# ARM_EURO_Platine4.net
KiCad netlist of a schematic drawn in Altium Designer
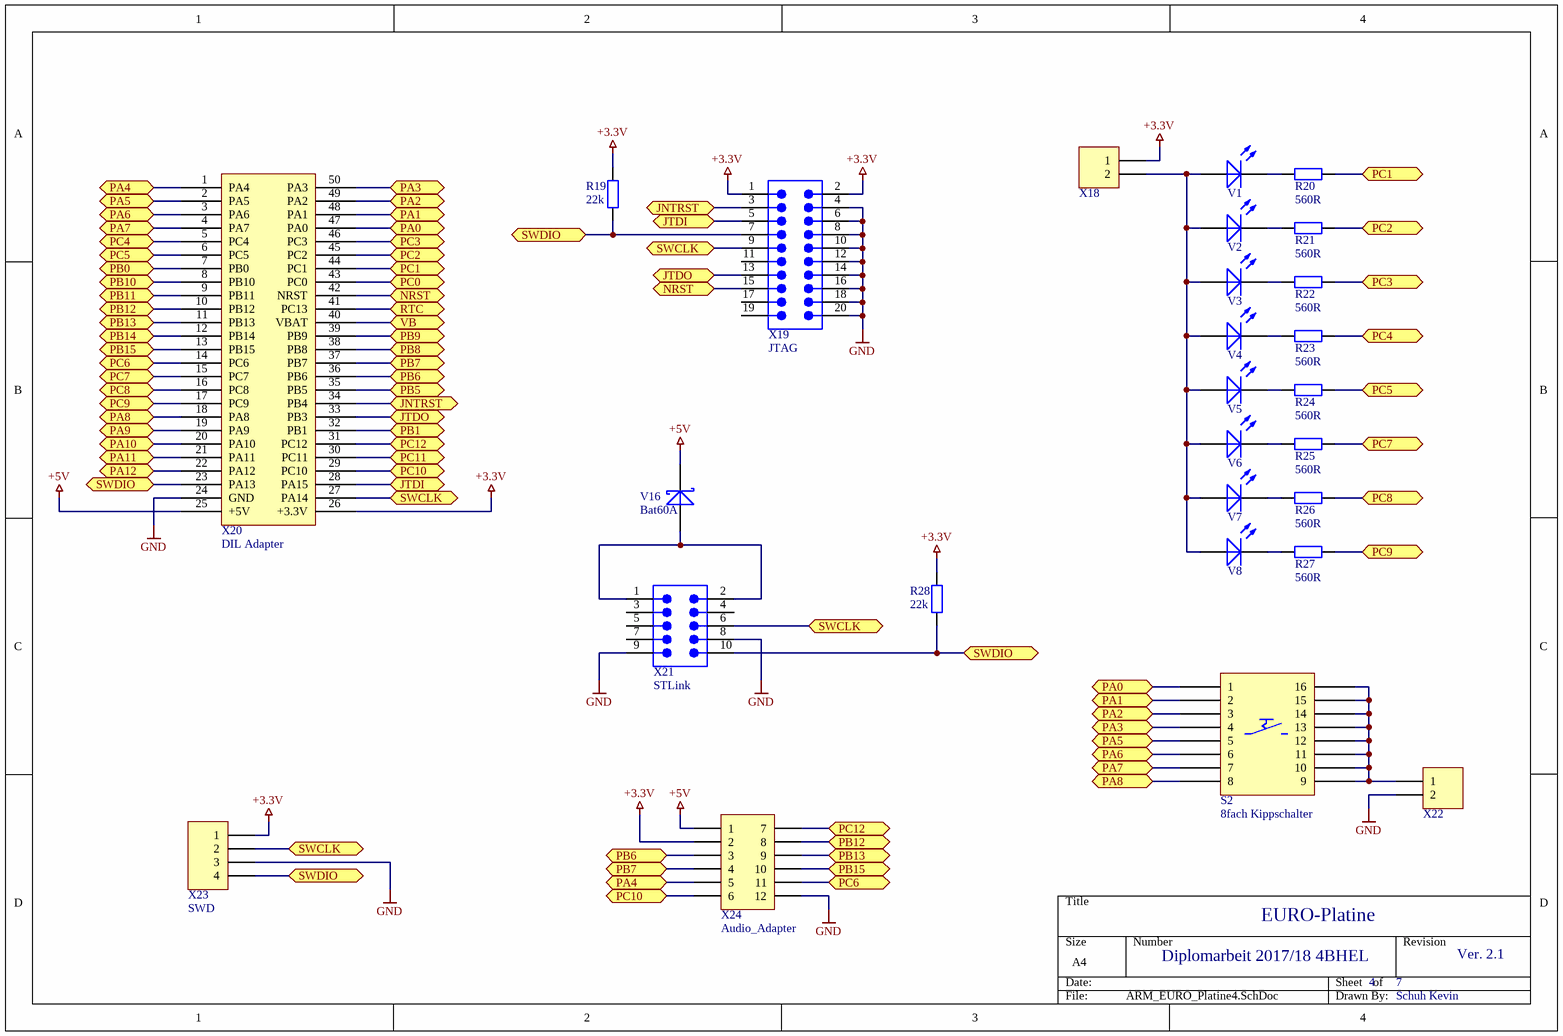
[diagram p0: ARM_EURO_Platine4.SchDoc]

(export (version "E")
  (design (tool "Eeschema 10.0.6"))
  (components
    (comp (ref "R19")
      (value "22k")
      (footprint "0805_Res")
      (description "Resistor")
      (fields (field (name "Comment") "Res_SMD") (field (name "PUBLISHER") "Altium Limited"))
      (libsource (lib "") (part "Res_SMD_1"))
    )
    (comp (ref "R20")
      (value "560R")
      (footprint "0805_Res")
      (description "Resistor")
      (fields (field (name "Comment") "Res_SMD") (field (name "PUBLISHER") "Altium Limited"))
      (libsource (lib "ARM_Libary_EURO") (part "Res_SMD"))
    )
    (comp (ref "R21")
      (value "560R")
      (footprint "0805_Res")
      (description "Resistor")
      (fields (field (name "Comment") "Res_SMD") (field (name "PUBLISHER") "Altium Limited"))
      (libsource (lib "ARM_Libary_EURO") (part "Res_SMD"))
    )
    (comp (ref "R22")
      (value "560R")
      (footprint "0805_Res")
      (description "Resistor")
      (fields (field (name "Comment") "Res_SMD") (field (name "PUBLISHER") "Altium Limited"))
      (libsource (lib "ARM_Libary_EURO") (part "Res_SMD"))
    )
    (comp (ref "R23")
      (value "560R")
      (footprint "0805_Res")
      (description "Resistor")
      (fields (field (name "Comment") "Res_SMD") (field (name "PUBLISHER") "Altium Limited"))
      (libsource (lib "ARM_Libary_EURO") (part "Res_SMD"))
    )
    (comp (ref "R24")
      (value "560R")
      (footprint "0805_Res")
      (description "Resistor")
      (fields (field (name "Comment") "Res_SMD") (field (name "PUBLISHER") "Altium Limited"))
      (libsource (lib "ARM_Libary_EURO") (part "Res_SMD"))
    )
    (comp (ref "R25")
      (value "560R")
      (footprint "0805_Res")
      (description "Resistor")
      (fields (field (name "Comment") "Res_SMD") (field (name "PUBLISHER") "Altium Limited"))
      (libsource (lib "ARM_Libary_EURO") (part "Res_SMD"))
    )
    (comp (ref "R26")
      (value "560R")
      (footprint "0805_Res")
      (description "Resistor")
      (fields (field (name "Comment") "Res_SMD") (field (name "PUBLISHER") "Altium Limited"))
      (libsource (lib "ARM_Libary_EURO") (part "Res_SMD"))
    )
    (comp (ref "R27")
      (value "560R")
      (footprint "0805_Res")
      (description "Resistor")
      (fields (field (name "Comment") "Res_SMD") (field (name "PUBLISHER") "Altium Limited"))
      (libsource (lib "ARM_Libary_EURO") (part "Res_SMD"))
    )
    (comp (ref "R28")
      (value "22k")
      (footprint "0805_Res")
      (description "Resistor")
      (fields (field (name "Comment") "Res_SMD") (field (name "PUBLISHER") "Altium Limited"))
      (libsource (lib "") (part "Res_SMD_1"))
    )
    (comp (ref "S2")
      (value "8fach Kippschalter")
      (footprint "DIP_16")
      (libsource (lib "ARM_Libary_EURO") (part "Kippschalter_8fach"))
    )
    (comp (ref "V1")
      (value "LED")
      (footprint "0805_LED")
      (description "Typical RED, GREEN, YELLOW, AMBER GaAs LED")
      (fields (field (name "PUBLISHER") "Altium Limited"))
      (libsource (lib "ARM_Libary_EURO") (part "LED_SMD"))
    )
    (comp (ref "V2")
      (value "LED")
      (footprint "0805_LED")
      (description "Typical RED, GREEN, YELLOW, AMBER GaAs LED")
      (fields (field (name "PUBLISHER") "Altium Limited"))
      (libsource (lib "ARM_Libary_EURO") (part "LED_SMD"))
    )
    (comp (ref "V3")
      (value "LED")
      (footprint "0805_LED")
      (description "Typical RED, GREEN, YELLOW, AMBER GaAs LED")
      (fields (field (name "PUBLISHER") "Altium Limited"))
      (libsource (lib "ARM_Libary_EURO") (part "LED_SMD"))
    )
    (comp (ref "V4")
      (value "LED")
      (footprint "0805_LED")
      (description "Typical RED, GREEN, YELLOW, AMBER GaAs LED")
      (fields (field (name "PUBLISHER") "Altium Limited"))
      (libsource (lib "ARM_Libary_EURO") (part "LED_SMD"))
    )
    (comp (ref "V5")
      (value "LED")
      (footprint "0805_LED")
      (description "Typical RED, GREEN, YELLOW, AMBER GaAs LED")
      (fields (field (name "PUBLISHER") "Altium Limited"))
      (libsource (lib "ARM_Libary_EURO") (part "LED_SMD"))
    )
    (comp (ref "V6")
      (value "LED")
      (footprint "0805_LED")
      (description "Typical RED, GREEN, YELLOW, AMBER GaAs LED")
      (fields (field (name "PUBLISHER") "Altium Limited"))
      (libsource (lib "ARM_Libary_EURO") (part "LED_SMD"))
    )
    (comp (ref "V7")
      (value "LED")
      (footprint "0805_LED")
      (description "Typical RED, GREEN, YELLOW, AMBER GaAs LED")
      (fields (field (name "PUBLISHER") "Altium Limited"))
      (libsource (lib "ARM_Libary_EURO") (part "LED_SMD"))
    )
    (comp (ref "V8")
      (value "LED")
      (footprint "0805_LED")
      (description "Typical RED, GREEN, YELLOW, AMBER GaAs LED")
      (fields (field (name "PUBLISHER") "Altium Limited"))
      (libsource (lib "ARM_Libary_EURO") (part "LED_SMD"))
    )
    (comp (ref "V16")
      (value "Bat60A")
      (footprint "BAT254_Schottky")
      (description "Diode")
      (libsource (lib "ARM_Libary_EURO") (part "Bat60A"))
    )
    (comp (ref "X18")
      (value "Header")
      (footprint "HDR1X2")
      (description "Header, 2-Pin")
      (fields (field (name "PUBLISHER") "Altium Limited"))
      (libsource (lib "") (part "Header_2_1"))
    )
    (comp (ref "X19")
      (value "JTAG")
      (footprint "JTAG_90Grad")
      (fields (field (name "PUBLISHER") "Altium Limited"))
      (libsource (lib "ARM_Libary_EURO") (part "JTAG"))
    )
    (comp (ref "X20")
      (value "DIL Adapter")
      (footprint "DIL_Adapter_V03")
      (description "DIL Adapter 50 Pin")
      (libsource (lib "ARM_Libary_EURO") (part "DIL_Adapter_V03"))
    )
    (comp (ref "X21")
      (value "STLink")
      (footprint "STLink")
      (fields (field (name "PUBLISHER") "Altium Limited"))
      (libsource (lib "ARM_Libary_EURO") (part "STLink"))
    )
    (comp (ref "X22")
      (value "Header")
      (footprint "HDR1X2")
      (description "Header, 2-Pin")
      (fields (field (name "PUBLISHER") "Altium Limited"))
      (libsource (lib "ARM_Libary_EURO") (part "Header_2"))
    )
    (comp (ref "X23")
      (value "SWD")
      (footprint "HDR1X4_SWD")
      (description "Header, 4-Pin")
      (fields (field (name "PUBLISHER") "Altium Limited"))
      (libsource (lib "ARM_Libary_DIL") (part "SWD"))
    )
    (comp (ref "X24")
      (value "Audio_Adapter")
      (footprint "AUDIO_ADAPTER")
      (description "Header, 6-Pin, Dual row")
      (fields (field (name "PUBLISHER") "Altium Limited"))
      (libsource (lib "ARM_Libary_EURO") (part "Audio_Adapter"))
    )
  )
  (nets
    (net (code "1") (name "+3.3V") (class "Default")
      (node (ref "R19") (pin "2") (pinfunction "2_2") (pintype "passive"))
      (node (ref "R28") (pin "2") (pinfunction "2_2") (pintype "passive"))
      (node (ref "X18") (pin "1") (pinfunction "1_1") (pintype "passive"))
      (node (ref "X19") (pin "1") (pinfunction "1_1") (pintype "passive"))
      (node (ref "X19") (pin "2") (pinfunction "2_2") (pintype "passive"))
      (node (ref "X20") (pin "26") (pinfunction "+3.3V_26") (pintype "passive"))
      (node (ref "X23") (pin "1") (pinfunction "1_1") (pintype "passive"))
      (node (ref "X24") (pin "2") (pinfunction "2_2") (pintype "passive"))
    )
    (net (code "2") (name "+5V") (class "Default")
      (node (ref "V16") (pin "1") (pinfunction "1_1") (pintype "passive"))
      (node (ref "X20") (pin "25") (pinfunction "+5V_25") (pintype "passive"))
      (node (ref "X24") (pin "1") (pinfunction "1_1") (pintype "passive"))
    )
    (net (code "3") (name "/JNTRST") (class "Default")
      (node (ref "X19") (pin "3") (pinfunction "3_3") (pintype "passive"))
      (node (ref "X20") (pin "34") (pinfunction "PB4_34") (pintype "passive"))
    )
    (net (code "4") (name "/JTDI") (class "Default")
      (node (ref "X19") (pin "5") (pinfunction "5_5") (pintype "passive"))
      (node (ref "X20") (pin "28") (pinfunction "PA15_28") (pintype "passive"))
    )
    (net (code "5") (name "/JTDO") (class "Default")
      (node (ref "X19") (pin "13") (pinfunction "13_13") (pintype "passive"))
      (node (ref "X20") (pin "33") (pinfunction "PB3_33") (pintype "passive"))
    )
    (net (code "6") (name "/NRST") (class "Default")
      (node (ref "X19") (pin "15") (pinfunction "15_15") (pintype "passive"))
      (node (ref "X20") (pin "42") (pinfunction "NRST_42") (pintype "passive"))
    )
    (net (code "7") (name "/PA0") (class "Default")
      (node (ref "S2") (pin "1") (pinfunction "1_1") (pintype "passive"))
      (node (ref "X20") (pin "47") (pinfunction "PA0_47") (pintype "passive"))
    )
    (net (code "8") (name "/PA1") (class "Default")
      (node (ref "S2") (pin "2") (pinfunction "2_2") (pintype "passive"))
      (node (ref "X20") (pin "48") (pinfunction "PA1_48") (pintype "passive"))
    )
    (net (code "9") (name "/PA2") (class "Default")
      (node (ref "S2") (pin "3") (pinfunction "3_3") (pintype "passive"))
      (node (ref "X20") (pin "49") (pinfunction "PA2_49") (pintype "passive"))
    )
    (net (code "10") (name "/PA3") (class "Default")
      (node (ref "S2") (pin "4") (pinfunction "4_4") (pintype "passive"))
      (node (ref "X20") (pin "50") (pinfunction "PA3_50") (pintype "passive"))
    )
    (net (code "11") (name "/PA4") (class "Default")
      (node (ref "X20") (pin "1") (pinfunction "PA4_1") (pintype "passive"))
      (node (ref "X24") (pin "5") (pinfunction "5_5") (pintype "passive"))
    )
    (net (code "12") (name "/PA5") (class "Default")
      (node (ref "S2") (pin "5") (pinfunction "5_5") (pintype "passive"))
      (node (ref "X20") (pin "2") (pinfunction "PA5_2") (pintype "passive"))
    )
    (net (code "13") (name "/PA6") (class "Default")
      (node (ref "S2") (pin "6") (pinfunction "6_6") (pintype "passive"))
      (node (ref "X20") (pin "3") (pinfunction "PA6_3") (pintype "passive"))
    )
    (net (code "14") (name "/PA7") (class "Default")
      (node (ref "S2") (pin "7") (pinfunction "7_7") (pintype "passive"))
      (node (ref "X20") (pin "4") (pinfunction "PA7_4") (pintype "passive"))
    )
    (net (code "15") (name "/PA8") (class "Default")
      (node (ref "S2") (pin "8") (pinfunction "8_8") (pintype "passive"))
      (node (ref "X20") (pin "18") (pinfunction "PA8_18") (pintype "passive"))
    )
    (net (code "16") (name "/PA9") (class "Default")
      (node (ref "X20") (pin "19") (pinfunction "PA9_19") (pintype "passive"))
    )
    (net (code "17") (name "/PA10") (class "Default")
      (node (ref "X20") (pin "20") (pinfunction "PA10_20") (pintype "passive"))
    )
    (net (code "18") (name "/PA11") (class "Default")
      (node (ref "X20") (pin "21") (pinfunction "PA11_21") (pintype "passive"))
    )
    (net (code "19") (name "/PA12") (class "Default")
      (node (ref "X20") (pin "22") (pinfunction "PA12_22") (pintype "passive"))
    )
    (net (code "20") (name "/PB0") (class "Default")
      (node (ref "X20") (pin "7") (pinfunction "PB0_7") (pintype "passive"))
    )
    (net (code "21") (name "/PB1") (class "Default")
      (node (ref "X20") (pin "32") (pinfunction "PB1_32") (pintype "passive"))
    )
    (net (code "22") (name "/PB5") (class "Default")
      (node (ref "X20") (pin "35") (pinfunction "PB5_35") (pintype "passive"))
    )
    (net (code "23") (name "/PB6") (class "Default")
      (node (ref "X20") (pin "36") (pinfunction "PB6_36") (pintype "passive"))
      (node (ref "X24") (pin "3") (pinfunction "3_3") (pintype "passive"))
    )
    (net (code "24") (name "/PB7") (class "Default")
      (node (ref "X20") (pin "37") (pinfunction "PB7_37") (pintype "passive"))
      (node (ref "X24") (pin "4") (pinfunction "4_4") (pintype "passive"))
    )
    (net (code "25") (name "/PB8") (class "Default")
      (node (ref "X20") (pin "38") (pinfunction "PB8_38") (pintype "passive"))
    )
    (net (code "26") (name "/PB9") (class "Default")
      (node (ref "X20") (pin "39") (pinfunction "PB9_39") (pintype "passive"))
    )
    (net (code "27") (name "/PB10") (class "Default")
      (node (ref "X20") (pin "8") (pinfunction "PB10_8") (pintype "passive"))
    )
    (net (code "28") (name "/PB11") (class "Default")
      (node (ref "X20") (pin "9") (pinfunction "PB11_9") (pintype "passive"))
    )
    (net (code "29") (name "/PB12") (class "Default")
      (node (ref "X20") (pin "10") (pinfunction "PB12_10") (pintype "passive"))
      (node (ref "X24") (pin "8") (pinfunction "8_8") (pintype "passive"))
    )
    (net (code "30") (name "/PB13") (class "Default")
      (node (ref "X20") (pin "11") (pinfunction "PB13_11") (pintype "passive"))
      (node (ref "X24") (pin "9") (pinfunction "9_9") (pintype "passive"))
    )
    (net (code "31") (name "/PB14") (class "Default")
      (node (ref "X20") (pin "12") (pinfunction "PB14_12") (pintype "passive"))
    )
    (net (code "32") (name "/PB15") (class "Default")
      (node (ref "X20") (pin "13") (pinfunction "PB15_13") (pintype "passive"))
      (node (ref "X24") (pin "10") (pinfunction "10_10") (pintype "passive"))
    )
    (net (code "33") (name "/PC0") (class "Default")
      (node (ref "X20") (pin "43") (pinfunction "PC0_43") (pintype "passive"))
    )
    (net (code "34") (name "/PC1") (class "Default")
      (node (ref "R20") (pin "2") (pinfunction "2_2") (pintype "passive"))
      (node (ref "X20") (pin "44") (pinfunction "PC1_44") (pintype "passive"))
    )
    (net (code "35") (name "/PC2") (class "Default")
      (node (ref "R21") (pin "2") (pinfunction "2_2") (pintype "passive"))
      (node (ref "X20") (pin "45") (pinfunction "PC2_45") (pintype "passive"))
    )
    (net (code "36") (name "/PC3") (class "Default")
      (node (ref "R22") (pin "2") (pinfunction "2_2") (pintype "passive"))
      (node (ref "X20") (pin "46") (pinfunction "PC3_46") (pintype "passive"))
    )
    (net (code "37") (name "/PC4") (class "Default")
      (node (ref "R23") (pin "2") (pinfunction "2_2") (pintype "passive"))
      (node (ref "X20") (pin "5") (pinfunction "PC4_5") (pintype "passive"))
    )
    (net (code "38") (name "/PC5") (class "Default")
      (node (ref "R24") (pin "2") (pinfunction "2_2") (pintype "passive"))
      (node (ref "X20") (pin "6") (pinfunction "PC5_6") (pintype "passive"))
    )
    (net (code "39") (name "/PC6") (class "Default")
      (node (ref "X20") (pin "14") (pinfunction "PC6_14") (pintype "passive"))
      (node (ref "X24") (pin "11") (pinfunction "11_11") (pintype "passive"))
    )
    (net (code "40") (name "/PC7") (class "Default")
      (node (ref "R25") (pin "2") (pinfunction "2_2") (pintype "passive"))
      (node (ref "X20") (pin "15") (pinfunction "PC7_15") (pintype "passive"))
    )
    (net (code "41") (name "/PC8") (class "Default")
      (node (ref "R26") (pin "2") (pinfunction "2_2") (pintype "passive"))
      (node (ref "X20") (pin "16") (pinfunction "PC8_16") (pintype "passive"))
    )
    (net (code "42") (name "/PC9") (class "Default")
      (node (ref "R27") (pin "2") (pinfunction "2_2") (pintype "passive"))
      (node (ref "X20") (pin "17") (pinfunction "PC9_17") (pintype "passive"))
    )
    (net (code "43") (name "/PC10") (class "Default")
      (node (ref "X20") (pin "29") (pinfunction "PC10_29") (pintype "passive"))
      (node (ref "X24") (pin "6") (pinfunction "6_6") (pintype "passive"))
    )
    (net (code "44") (name "/PC11") (class "Default")
      (node (ref "X20") (pin "30") (pinfunction "PC11_30") (pintype "passive"))
    )
    (net (code "45") (name "/PC12") (class "Default")
      (node (ref "X20") (pin "31") (pinfunction "PC12_31") (pintype "passive"))
      (node (ref "X24") (pin "7") (pinfunction "7_7") (pintype "passive"))
    )
    (net (code "46") (name "/RTC") (class "Default")
      (node (ref "X20") (pin "41") (pinfunction "PC13_41") (pintype "passive"))
    )
    (net (code "47") (name "/SWCLK") (class "Default")
      (node (ref "X19") (pin "9") (pinfunction "9_9") (pintype "passive"))
      (node (ref "X20") (pin "27") (pinfunction "PA14_27") (pintype "passive"))
      (node (ref "X21") (pin "6") (pinfunction "6_6") (pintype "passive"))
      (node (ref "X23") (pin "2") (pinfunction "2_2") (pintype "passive"))
    )
    (net (code "48") (name "/SWDIO") (class "Default")
      (node (ref "R19") (pin "1") (pinfunction "1_1") (pintype "passive"))
      (node (ref "R28") (pin "1") (pinfunction "1_1") (pintype "passive"))
      (node (ref "X19") (pin "7") (pinfunction "7_7") (pintype "passive"))
      (node (ref "X20") (pin "23") (pinfunction "PA13_23") (pintype "passive"))
      (node (ref "X21") (pin "10") (pinfunction "10_10") (pintype "passive"))
      (node (ref "X23") (pin "4") (pinfunction "4_4") (pintype "passive"))
    )
    (net (code "49") (name "/VB") (class "Default")
      (node (ref "X20") (pin "40") (pinfunction "VBAT_40") (pintype "passive"))
    )
    (net (code "50") (name "GND") (class "Default")
      (node (ref "X19") (pin "10") (pinfunction "10_10") (pintype "passive"))
      (node (ref "X19") (pin "12") (pinfunction "12_12") (pintype "passive"))
      (node (ref "X19") (pin "14") (pinfunction "14_14") (pintype "passive"))
      (node (ref "X19") (pin "16") (pinfunction "16_16") (pintype "passive"))
      (node (ref "X19") (pin "18") (pinfunction "18_18") (pintype "passive"))
      (node (ref "X19") (pin "20") (pinfunction "20_20") (pintype "passive"))
      (node (ref "X19") (pin "4") (pinfunction "4_4") (pintype "passive"))
      (node (ref "X19") (pin "6") (pinfunction "6_6") (pintype "passive"))
      (node (ref "X19") (pin "8") (pinfunction "8_8") (pintype "passive"))
      (node (ref "X20") (pin "24") (pinfunction "GND_24") (pintype "passive"))
      (node (ref "X21") (pin "8") (pinfunction "8_8") (pintype "passive"))
      (node (ref "X21") (pin "9") (pinfunction "9_9") (pintype "passive"))
      (node (ref "X22") (pin "2") (pinfunction "2_2") (pintype "passive"))
      (node (ref "X23") (pin "3") (pinfunction "3_3") (pintype "passive"))
      (node (ref "X24") (pin "12") (pinfunction "12_12") (pintype "passive"))
    )
    (net (code "51") (name "Net-(S2-Pad10)") (class "Default")
      (node (ref "S2") (pin "10") (pinfunction "10_10") (pintype "passive"))
      (node (ref "S2") (pin "11") (pinfunction "11_11") (pintype "passive"))
      (node (ref "S2") (pin "12") (pinfunction "12_12") (pintype "passive"))
      (node (ref "S2") (pin "13") (pinfunction "13_13") (pintype "passive"))
      (node (ref "S2") (pin "14") (pinfunction "14_14") (pintype "passive"))
      (node (ref "S2") (pin "15") (pinfunction "15_15") (pintype "passive"))
      (node (ref "S2") (pin "16") (pinfunction "16_16") (pintype "passive"))
      (node (ref "S2") (pin "9") (pinfunction "9_9") (pintype "passive"))
      (node (ref "X22") (pin "1") (pinfunction "1_1") (pintype "passive"))
    )
    (net (code "52") (name "Net-(V1-A)") (class "Default")
      (node (ref "V1") (pin "1") (pinfunction "A_1") (pintype "passive"))
      (node (ref "V2") (pin "1") (pinfunction "A_1") (pintype "passive"))
      (node (ref "V3") (pin "1") (pinfunction "A_1") (pintype "passive"))
      (node (ref "V4") (pin "1") (pinfunction "A_1") (pintype "passive"))
      (node (ref "V5") (pin "1") (pinfunction "A_1") (pintype "passive"))
      (node (ref "V6") (pin "1") (pinfunction "A_1") (pintype "passive"))
      (node (ref "V7") (pin "1") (pinfunction "A_1") (pintype "passive"))
      (node (ref "V8") (pin "1") (pinfunction "A_1") (pintype "passive"))
      (node (ref "X18") (pin "2") (pinfunction "2_2") (pintype "passive"))
    )
    (net (code "53") (name "Net-(V1-K)") (class "Default")
      (node (ref "R20") (pin "1") (pinfunction "1_1") (pintype "passive"))
      (node (ref "V1") (pin "2") (pinfunction "K_2") (pintype "passive"))
    )
    (net (code "54") (name "Net-(V2-K)") (class "Default")
      (node (ref "R21") (pin "1") (pinfunction "1_1") (pintype "passive"))
      (node (ref "V2") (pin "2") (pinfunction "K_2") (pintype "passive"))
    )
    (net (code "55") (name "Net-(V3-K)") (class "Default")
      (node (ref "R22") (pin "1") (pinfunction "1_1") (pintype "passive"))
      (node (ref "V3") (pin "2") (pinfunction "K_2") (pintype "passive"))
    )
    (net (code "56") (name "Net-(V4-K)") (class "Default")
      (node (ref "R23") (pin "1") (pinfunction "1_1") (pintype "passive"))
      (node (ref "V4") (pin "2") (pinfunction "K_2") (pintype "passive"))
    )
    (net (code "57") (name "Net-(V5-K)") (class "Default")
      (node (ref "R24") (pin "1") (pinfunction "1_1") (pintype "passive"))
      (node (ref "V5") (pin "2") (pinfunction "K_2") (pintype "passive"))
    )
    (net (code "58") (name "Net-(V6-K)") (class "Default")
      (node (ref "R25") (pin "1") (pinfunction "1_1") (pintype "passive"))
      (node (ref "V6") (pin "2") (pinfunction "K_2") (pintype "passive"))
    )
    (net (code "59") (name "Net-(V7-K)") (class "Default")
      (node (ref "R26") (pin "1") (pinfunction "1_1") (pintype "passive"))
      (node (ref "V7") (pin "2") (pinfunction "K_2") (pintype "passive"))
    )
    (net (code "60") (name "Net-(V8-K)") (class "Default")
      (node (ref "R27") (pin "1") (pinfunction "1_1") (pintype "passive"))
      (node (ref "V8") (pin "2") (pinfunction "K_2") (pintype "passive"))
    )
    (net (code "61") (name "Net-(V16-Pad2)") (class "Default")
      (node (ref "V16") (pin "2") (pinfunction "2_2") (pintype "passive"))
      (node (ref "X21") (pin "1") (pinfunction "1_1") (pintype "passive"))
      (node (ref "X21") (pin "2") (pinfunction "2_2") (pintype "passive"))
    )
    (net (code "62") (name "unconnected-(X19-Pad11)") (class "Default")
      (node (ref "X19") (pin "11") (pinfunction "11_11") (pintype "passive"))
    )
    (net (code "63") (name "unconnected-(X19-Pad17)") (class "Default")
      (node (ref "X19") (pin "17") (pinfunction "17_17") (pintype "passive"))
    )
    (net (code "64") (name "unconnected-(X19-Pad19)") (class "Default")
      (node (ref "X19") (pin "19") (pinfunction "19_19") (pintype "passive"))
    )
    (net (code "65") (name "unconnected-(X21-Pad3)") (class "Default")
      (node (ref "X21") (pin "3") (pinfunction "3_3") (pintype "passive"))
    )
    (net (code "66") (name "unconnected-(X21-Pad4)") (class "Default")
      (node (ref "X21") (pin "4") (pinfunction "4_4") (pintype "passive"))
    )
    (net (code "67") (name "unconnected-(X21-Pad5)") (class "Default")
      (node (ref "X21") (pin "5") (pinfunction "5_5") (pintype "passive"))
    )
    (net (code "68") (name "unconnected-(X21-Pad7)") (class "Default")
      (node (ref "X21") (pin "7") (pinfunction "7_7") (pintype "passive"))
    )
  )
)
